# 1V8_3V3_5V.net
KiCad netlist of a schematic drawn in Altium Designer
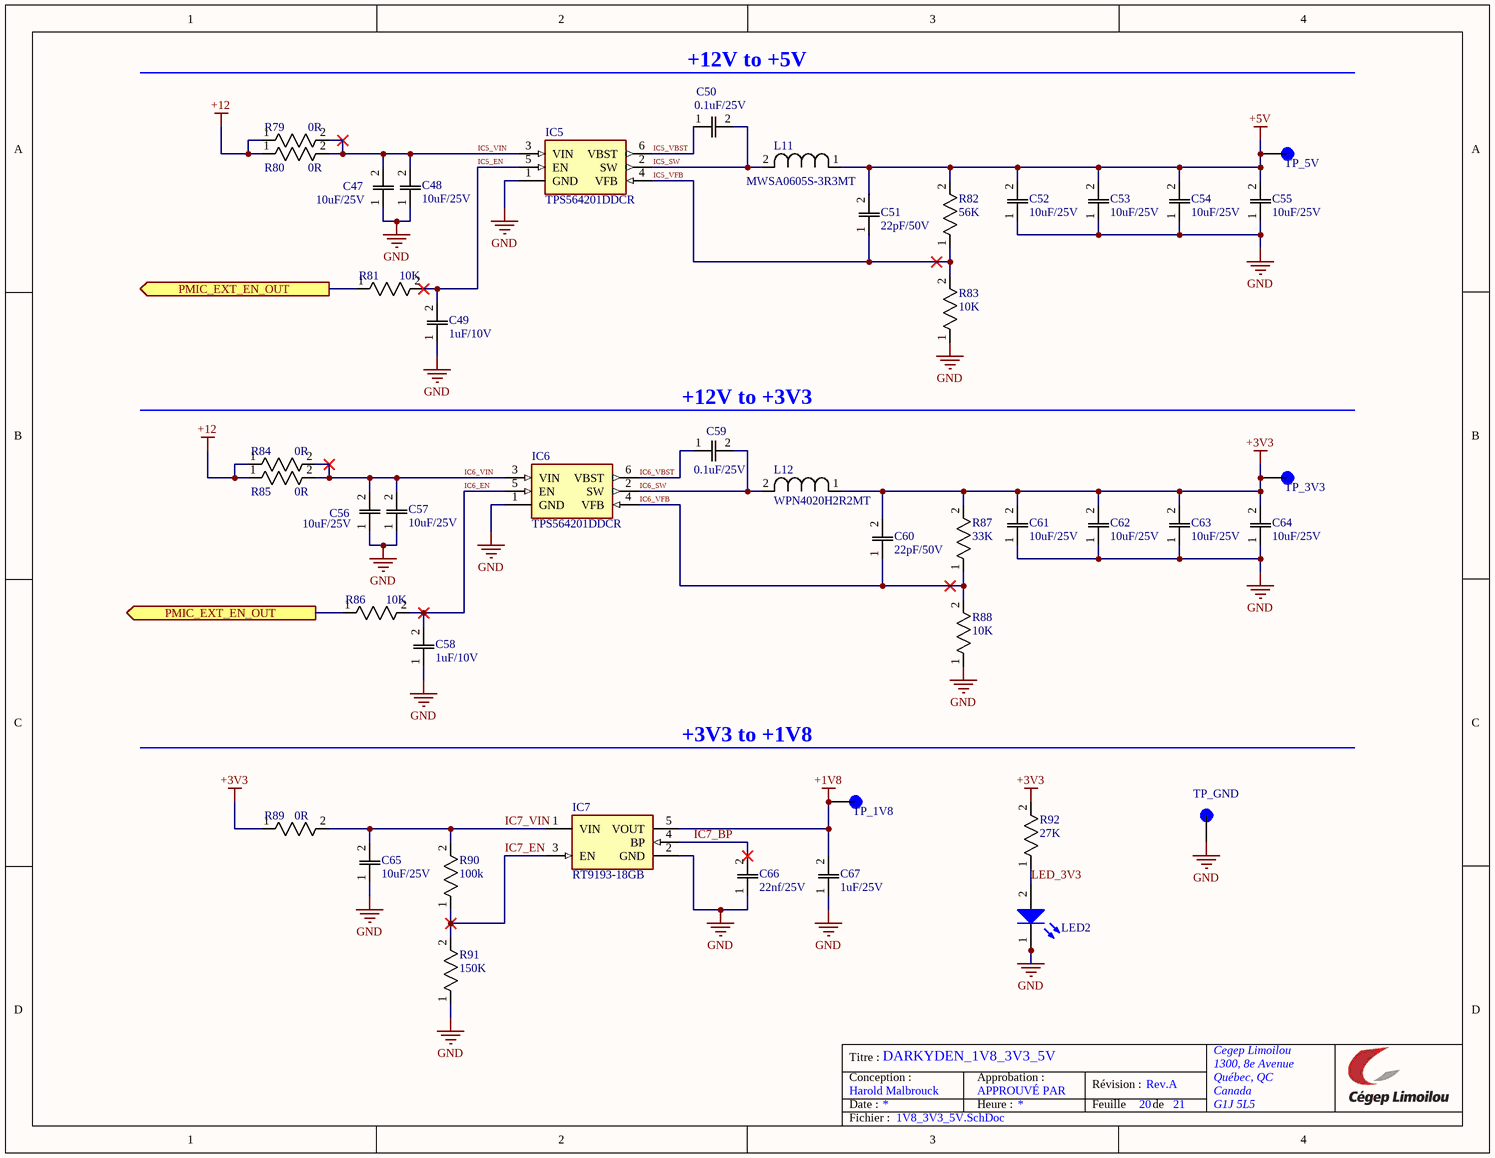
[diagram p0: 1V8_3V3_5V.SchDoc]

(export (version "E")
  (design (tool "Eeschema 10.0.6"))
  (components
    (comp (ref "C47")
      (value "10uF/25V")
      (footprint "C0805")
      (description "10uF / 25 VDC, +85degC, X5R Dielec, +/-10% ¦ KEMET C0805C106K3PACTU 0805")
      (fields
        (field (name "MANUFACTURER") "KEMET")
        (field (name "MANUFACTURER PART NUMBER") "C0805C106K3PACTU")
      )
      (libsource (lib "DARKYDEN") (part "C0805C106K3PACTU"))
    )
    (comp (ref "C48")
      (value "10uF/25V")
      (footprint "C0805")
      (description "10uF / 25 VDC, +85degC, X5R Dielec, +/-10% ¦ KEMET C0805C106K3PACTU 0805")
      (fields
        (field (name "MANUFACTURER") "KEMET")
        (field (name "MANUFACTURER PART NUMBER") "C0805C106K3PACTU")
      )
      (libsource (lib "DARKYDEN") (part "C0805C106K3PACTU"))
    )
    (comp (ref "C49")
      (value "1uF/10V")
      (footprint "C0805")
      (description "Multilayer Ceramic Capacitors MLCC - SMD/SMT 10V 1uF X7R 0805 10%")
      (fields
        (field (name "MANUFACTURER") "KEMET")
        (field (name "MANUFACTURER PART NUMBER") "C0805C105K3RACTU")
      )
      (libsource (lib "DARKYDEN") (part "C0805C105K8RACTU"))
    )
    (comp (ref "C50")
      (value "0.1uF/25V")
      (footprint "c0805")
      (description "0.1uF 25V X7R 10% SMD 0805 125C Plastic T/R")
      (fields
        (field (name "MANUFACTURER") "KEMET")
        (field (name "MANUFACTURER PART NUMBER") "C0805C104K5RACTU")
      )
      (libsource (lib "DARKYDEN") (part "C0805C104K3RACTU"))
    )
    (comp (ref "C51")
      (value "22pF/50V")
      (footprint "C0805")
      (description "Cap Ceramic 22pF 50V X7R 5% Pad SMD 0805 125°C T/R")
      (fields
        (field (name "MANUFACTURER") "KEMET")
        (field (name "MANUFACTURER PART NUMBER") "C0805C220J5RACTU")
      )
      (libsource (lib "DARKYDEN") (part "C0805C220J5RACTU"))
    )
    (comp (ref "C52")
      (value "10uF/25V")
      (footprint "C0805")
      (description "10uF / 25 VDC, +85degC, X5R Dielec, +/-10% ¦ KEMET C0805C106K3PACTU 0805")
      (fields
        (field (name "MANUFACTURER") "KEMET")
        (field (name "MANUFACTURER PART NUMBER") "C0805C106K3PACTU")
      )
      (libsource (lib "DARKYDEN") (part "C0805C106K3PACTU"))
    )
    (comp (ref "C53")
      (value "10uF/25V")
      (footprint "C0805")
      (description "10uF / 25 VDC, +85degC, X5R Dielec, +/-10% ¦ KEMET C0805C106K3PACTU 0805")
      (fields
        (field (name "MANUFACTURER") "KEMET")
        (field (name "MANUFACTURER PART NUMBER") "C0805C106K3PACTU")
      )
      (libsource (lib "DARKYDEN") (part "C0805C106K3PACTU"))
    )
    (comp (ref "C54")
      (value "10uF/25V")
      (footprint "C0805")
      (description "10uF / 25 VDC, +85degC, X5R Dielec, +/-10% ¦ KEMET C0805C106K3PACTU 0805")
      (fields
        (field (name "MANUFACTURER") "KEMET")
        (field (name "MANUFACTURER PART NUMBER") "C0805C106K3PACTU")
      )
      (libsource (lib "DARKYDEN") (part "C0805C106K3PACTU"))
    )
    (comp (ref "C55")
      (value "10uF/25V")
      (footprint "C0805")
      (description "10uF / 25 VDC, +85degC, X5R Dielec, +/-10% ¦ KEMET C0805C106K3PACTU 0805")
      (fields
        (field (name "MANUFACTURER") "KEMET")
        (field (name "MANUFACTURER PART NUMBER") "C0805C106K3PACTU")
      )
      (libsource (lib "DARKYDEN") (part "C0805C106K3PACTU"))
    )
    (comp (ref "C56")
      (value "10uF/25V")
      (footprint "C0805")
      (description "10uF / 25 VDC, +85degC, X5R Dielec, +/-10% ¦ KEMET C0805C106K3PACTU 0805")
      (fields
        (field (name "MANUFACTURER") "KEMET")
        (field (name "MANUFACTURER PART NUMBER") "C0805C106K3PACTU")
      )
      (libsource (lib "DARKYDEN") (part "C0805C106K3PACTU"))
    )
    (comp (ref "C57")
      (value "10uF/25V")
      (footprint "C0805")
      (description "10uF / 25 VDC, +85degC, X5R Dielec, +/-10% ¦ KEMET C0805C106K3PACTU 0805")
      (fields
        (field (name "MANUFACTURER") "KEMET")
        (field (name "MANUFACTURER PART NUMBER") "C0805C106K3PACTU")
      )
      (libsource (lib "DARKYDEN") (part "C0805C106K3PACTU"))
    )
    (comp (ref "C58")
      (value "1uF/10V")
      (footprint "C0805")
      (description "Multilayer Ceramic Capacitors MLCC - SMD/SMT 10V 1uF X7R 0805 10%")
      (fields
        (field (name "MANUFACTURER") "KEMET")
        (field (name "MANUFACTURER PART NUMBER") "C0805C105K3RACTU")
      )
      (libsource (lib "DARKYDEN") (part "C0805C105K8RACTU"))
    )
    (comp (ref "C59")
      (value "0.1uF/25V")
      (footprint "c0805")
      (description "0.1uF 25V X7R 10% SMD 0805 125C Plastic T/R")
      (fields
        (field (name "MANUFACTURER") "KEMET")
        (field (name "MANUFACTURER PART NUMBER") "C0805C104K5RACTU")
      )
      (libsource (lib "DARKYDEN") (part "C0805C104K3RACTU"))
    )
    (comp (ref "C60")
      (value "22pF/50V")
      (footprint "C0805")
      (description "Cap Ceramic 22pF 50V X7R 5% Pad SMD 0805 125°C T/R")
      (fields
        (field (name "MANUFACTURER") "KEMET")
        (field (name "MANUFACTURER PART NUMBER") "C0805C220J5RACTU")
      )
      (libsource (lib "DARKYDEN") (part "C0805C220J5RACTU"))
    )
    (comp (ref "C61")
      (value "10uF/25V")
      (footprint "C0805")
      (description "10uF / 25 VDC, +85degC, X5R Dielec, +/-10% ¦ KEMET C0805C106K3PACTU 0805")
      (fields
        (field (name "MANUFACTURER") "KEMET")
        (field (name "MANUFACTURER PART NUMBER") "C0805C106K3PACTU")
      )
      (libsource (lib "DARKYDEN") (part "C0805C106K3PACTU"))
    )
    (comp (ref "C62")
      (value "10uF/25V")
      (footprint "C0805")
      (description "10uF / 25 VDC, +85degC, X5R Dielec, +/-10% ¦ KEMET C0805C106K3PACTU 0805")
      (fields
        (field (name "MANUFACTURER") "KEMET")
        (field (name "MANUFACTURER PART NUMBER") "C0805C106K3PACTU")
      )
      (libsource (lib "DARKYDEN") (part "C0805C106K3PACTU"))
    )
    (comp (ref "C63")
      (value "10uF/25V")
      (footprint "C0805")
      (description "10uF / 25 VDC, +85degC, X5R Dielec, +/-10% ¦ KEMET C0805C106K3PACTU 0805")
      (fields
        (field (name "MANUFACTURER") "KEMET")
        (field (name "MANUFACTURER PART NUMBER") "C0805C106K3PACTU")
      )
      (libsource (lib "DARKYDEN") (part "C0805C106K3PACTU"))
    )
    (comp (ref "C64")
      (value "10uF/25V")
      (footprint "C0805")
      (description "10uF / 25 VDC, +85degC, X5R Dielec, +/-10% ¦ KEMET C0805C106K3PACTU 0805")
      (fields
        (field (name "MANUFACTURER") "KEMET")
        (field (name "MANUFACTURER PART NUMBER") "C0805C106K3PACTU")
      )
      (libsource (lib "DARKYDEN") (part "C0805C106K3PACTU"))
    )
    (comp (ref "C65")
      (value "10uF/25V")
      (footprint "C0805")
      (description "10uF / 25 VDC, +85degC, X5R Dielec, +/-10% ¦ KEMET C0805C106K3PACTU 0805")
      (fields
        (field (name "MANUFACTURER") "KEMET")
        (field (name "MANUFACTURER PART NUMBER") "C0805C106K3PACTU")
      )
      (libsource (lib "DARKYDEN") (part "C0805C106K3PACTU"))
    )
    (comp (ref "C66")
      (value "22nf/25V")
      (footprint "C0805")
      (description "22nF, 25 V, 0805 [2012 Metric], 5%, C0G / NP0")
      (fields
        (field (name "MANUFACTURER") "KEMET")
        (field (name "MANUFACTURER PART NUMBER") "C0805C223J3GACTU")
      )
      (libsource (lib "DARKYDEN") (part "C0805C223J3GACTU"))
    )
    (comp (ref "C67")
      (value "1uF/25V")
      (footprint "C0805")
      (description "1 µF, 25 V (DC), ±10 %, SMD 0805, X7R, C0805C105K3RAC7800")
      (fields
        (field (name "MOUSER PART NUMBER") "80-C0805C105K3R")
        (field (name "ARROW PART NUMBER") "C0805C105K3RACTU")
      )
      (libsource (lib "DARKYDEN") (part "C0805C105K3RACTU"))
    )
    (comp (ref "IC5")
      (value "TPS564201DDCR")
      (footprint "SamacSys:SOT95P280X110-6N")
      (fields
        (field (name "MOUSER PART NUMBER") "595-TPS564201DDCR")
        (field (name "MANUFACTURER") "Texas Instruments")
      )
      (libsource (lib "SamacSys") (part "TPS564201DDCR"))
    )
    (comp (ref "IC6")
      (value "TPS564201DDCR")
      (footprint "SamacSys:SOT95P280X110-6N")
      (fields
        (field (name "MOUSER PART NUMBER") "595-TPS564201DDCR")
        (field (name "MANUFACTURER") "Texas Instruments")
      )
      (libsource (lib "SamacSys") (part "TPS564201DDCR"))
    )
    (comp (ref "IC7")
      (value "RT9193-18GB")
      (footprint "SamacSys:SOT94P279X130-5N")
      (description "Linear Voltage Regulator IC Positive Fixed 1.8V Output 300mA SOT-23-5")
      (fields (field (name "MOUSER PART NUMBER") "835-RT9193-18GB"))
      (libsource (lib "SamacSys") (part "RT9193-18GB"))
    )
    (comp (ref "L11")
      (value "MWSA0605S-3R3MT")
      (footprint "IND_MWSA0603S_SNL")
      (description "3.3 µH Shielded Drum Core, Wirewound Inductor 8.5 A 22mOhm Max Nonstandard")
      (libsource (lib "MWSA0603S-XRXMT") (part "MWSA0605S-3R3MT"))
    )
    (comp (ref "L12")
      (value "WPN4020H2R2MT")
      (footprint "WPN4020H2R2MT:IND_WPN4020H_SNL")
      (description "2.2 µH Shielded Drum Core, Wirewound Inductor 4.3 A 48mOhm Max Nonstandard")
      (fields (field (name "MANUFACTURER") "Sunlord"))
      (libsource (lib "DARKYDEN") (part "WPN4020H2R2MT"))
    )
    (comp (ref "LED2")
      (value "Blue, 3.2V, 140°")
      (footprint "WL-SMCD_0603")
      (description "WL-SMCD Mono-color Chip LED Diffused, SMT, size 0603, Blue, 3.2V, 140°")
      (fields
        (field (name "MANUFACTURER PART NUMBER") "150060BS55040")
        (field (name "MANUFACTURER") "Wurth Elektronik")
      )
      (libsource (lib "0603_LED") (part "BLUE"))
    )
    (comp (ref "R79")
      (value "0R")
      (footprint "SamacSys:RESC1608X55N")
      (description "Zero Ohm Resistor, Jumper, 0603 [1608 Metric], Thick Film, 100 mW, 1 A, Surface Mount")
      (fields
        (field (name "MOUSER PART NUMBER") "667-ERJ-3GEY0R00V")
        (field (name "ARROW PART NUMBER") "ERJ-3GEY0R00V")
      )
      (libsource (lib "DARKYDEN") (part "ERJ-3GEY0R00V"))
    )
    (comp (ref "R80")
      (value "0R")
      (footprint "SamacSys:RESC1608X55N")
      (description "Zero Ohm Resistor, Jumper, 0603 [1608 Metric], Thick Film, 100 mW, 1 A, Surface Mount")
      (fields
        (field (name "MOUSER PART NUMBER") "667-ERJ-3GEY0R00V")
        (field (name "ARROW PART NUMBER") "ERJ-3GEY0R00V")
      )
      (libsource (lib "DARKYDEN") (part "ERJ-3GEY0R00V"))
    )
    (comp (ref "R81")
      (value "10K")
      (footprint "SamacSys:RESC1608X55N")
      (description "10K Ohm 5% Res Thick Film 0603  0.1W(1/10W) ±200ppm/C Pad SMD Automotive T/R")
      (fields
        (field (name "MOUSER PART NUMBER") "667-ERJ-3GEYJ103V")
        (field (name "ARROW PART NUMBER") "ERJ-3GEYJ103V")
      )
      (libsource (lib "DARKYDEN") (part "ERJ-3GEYJ103V"))
    )
    (comp (ref "R82")
      (value "56K")
      (footprint "SamacSys:RESC1608X55N")
      (description "56K Ohm 1% 1/10W +/-100ppm/ßC Molded SMD Punched Carrier T/R")
      (fields
        (field (name "MOUSER PART NUMBER") "667-ERJ-3EKF5602V")
        (field (name "ARROW PART NUMBER") "ERJ-3EKF5602V")
      )
      (libsource (lib "DARKYDEN") (part "ERJ-3EKF5602V"))
    )
    (comp (ref "R83")
      (value "10K")
      (footprint "SamacSys:RESC1608X55N")
      (description "10K Ohm 5% Res Thick Film 0603  0.1W(1/10W) ±200ppm/C Pad SMD Automotive T/R")
      (fields
        (field (name "MOUSER PART NUMBER") "667-ERJ-3GEYJ103V")
        (field (name "ARROW PART NUMBER") "ERJ-3GEYJ103V")
      )
      (libsource (lib "DARKYDEN") (part "ERJ-3GEYJ103V"))
    )
    (comp (ref "R84")
      (value "0R")
      (footprint "SamacSys:RESC1608X55N")
      (description "Zero Ohm Resistor, Jumper, 0603 [1608 Metric], Thick Film, 100 mW, 1 A, Surface Mount")
      (fields
        (field (name "MOUSER PART NUMBER") "667-ERJ-3GEY0R00V")
        (field (name "ARROW PART NUMBER") "ERJ-3GEY0R00V")
      )
      (libsource (lib "DARKYDEN") (part "ERJ-3GEY0R00V"))
    )
    (comp (ref "R85")
      (value "0R")
      (footprint "SamacSys:RESC1608X55N")
      (description "Zero Ohm Resistor, Jumper, 0603 [1608 Metric], Thick Film, 100 mW, 1 A, Surface Mount")
      (fields
        (field (name "MOUSER PART NUMBER") "667-ERJ-3GEY0R00V")
        (field (name "ARROW PART NUMBER") "ERJ-3GEY0R00V")
      )
      (libsource (lib "DARKYDEN") (part "ERJ-3GEY0R00V"))
    )
    (comp (ref "R86")
      (value "10K")
      (footprint "SamacSys:RESC1608X55N")
      (description "10K Ohm 5% Res Thick Film 0603  0.1W(1/10W) ±200ppm/C Pad SMD Automotive T/R")
      (fields
        (field (name "MOUSER PART NUMBER") "667-ERJ-3GEYJ103V")
        (field (name "ARROW PART NUMBER") "ERJ-3GEYJ103V")
      )
      (libsource (lib "DARKYDEN") (part "ERJ-3GEYJ103V"))
    )
    (comp (ref "R87")
      (value "33K")
      (footprint "SamacSys:RESC1608X55N")
      (description "33K Ohm 0603  5% 0.1W(1/10W) +/-200ppm/ßC SMD Automotive T/R")
      (fields
        (field (name "MOUSER PART NUMBER") "667-ERJ-3GEYJ333V")
        (field (name "MANUFACTURER") "Panasonic")
      )
      (libsource (lib "DARKYDEN") (part "ERJ-3GEYJ333V"))
    )
    (comp (ref "R88")
      (value "10K")
      (footprint "SamacSys:RESC1608X55N")
      (description "10K Ohm 5% Res Thick Film 0603  0.1W(1/10W) ±200ppm/C Pad SMD Automotive T/R")
      (fields
        (field (name "MOUSER PART NUMBER") "667-ERJ-3GEYJ103V")
        (field (name "ARROW PART NUMBER") "ERJ-3GEYJ103V")
      )
      (libsource (lib "DARKYDEN") (part "ERJ-3GEYJ103V"))
    )
    (comp (ref "R89")
      (value "0R")
      (footprint "SamacSys:RESC1608X55N")
      (description "Zero Ohm Resistor, Jumper, 0603 [1608 Metric], Thick Film, 100 mW, 1 A, Surface Mount")
      (fields
        (field (name "MOUSER PART NUMBER") "667-ERJ-3GEY0R00V")
        (field (name "ARROW PART NUMBER") "ERJ-3GEY0R00V")
      )
      (libsource (lib "DARKYDEN") (part "ERJ-3GEY0R00V"))
    )
    (comp (ref "R90")
      (value "100k")
      (footprint "SamacSys:RESC1608X55N")
      (description "100K Ohm 5%  Res Thick Film 0603 1/10W +/-200ppm/ßC Molded SMD Punched Carrier T/R")
      (fields
        (field (name "MOUSER PART NUMBER") "667-ERJ-3GEYJ104V")
        (field (name "ARROW PART NUMBER") "ERJ-3GEYJ104V")
      )
      (libsource (lib "DARKYDEN") (part "ERJ-3GEYJ104V"))
    )
    (comp (ref "R91")
      (value "150K")
      (footprint "SamacSys:RESC1608X55N")
      (description "150 kOhm, ± 5%, 100 mW, 0603 [1608 Metric], Thick Film, General Purpose")
      (fields
        (field (name "MOUSER PART NUMBER") "667-ERJ-3GEYJ154V")
        (field (name "ARROW PART NUMBER") "ERJ-3GEYJ154V")
      )
      (libsource (lib "DARKYDEN") (part "ERJ-3GEYJ154V"))
    )
    (comp (ref "R92")
      (value "27K")
      (footprint "RESC1608X55N")
      (description "27K Ohm 1% 1/10W 0603 ±100ppm/°C Molded SMD Punched Carrier T/R")
      (fields
        (field (name "MANUFACTURER") "Panasonic")
        (field (name "MANUFACTURER PART NUMBER") "ERJ-3EKF2702V")
      )
      (libsource (lib "DARKYDEN") (part "ERJ-3EKF2702V"))
    )
    (comp (ref "TP_1V8")
      (value "~")
      (footprint "KEYSTONE_5006")
      (description "Test Point Compact THM PC .350 L .125 OD Heat Resistant Nylon 46 Black ¦ Keystone Electronics 5006")
      (fields (field (name "MF") "Keystone Electronics Corp.") (field (name "MP") "5006"))
      (libsource (lib "DARKYDEN") (part "5006"))
    )
    (comp (ref "TP_3V3")
      (value "~")
      (footprint "KEYSTONE_5006")
      (description "Test Point Compact THM PC .350 L .125 OD Heat Resistant Nylon 46 Black ¦ Keystone Electronics 5006")
      (fields (field (name "MF") "Keystone Electronics Corp.") (field (name "MP") "5006"))
      (libsource (lib "DARKYDEN") (part "5006"))
    )
    (comp (ref "TP_5V")
      (value "~")
      (footprint "KEYSTONE_5006")
      (description "Test Point Compact THM PC .350 L .125 OD Heat Resistant Nylon 46 Black ¦ Keystone Electronics 5006")
      (fields (field (name "MF") "Keystone Electronics Corp.") (field (name "MP") "5006"))
      (libsource (lib "DARKYDEN") (part "5006"))
    )
    (comp (ref "TP_GND")
      (value "~")
      (footprint "KEYSTONE_5006")
      (description "Test Point Compact THM PC .350 L .125 OD Heat Resistant Nylon 46 Black ¦ Keystone Electronics 5006")
      (fields (field (name "MF") "Keystone Electronics Corp.") (field (name "MP") "5006"))
      (libsource (lib "DARKYDEN") (part "5006"))
    )
  )
  (nets
    (net (code "1") (name "+1V8") (class "Default")
      (node (ref "C67") (pin "2") (pinfunction "2_2") (pintype "passive"))
      (node (ref "IC7") (pin "5") (pinfunction "VOUT_5") (pintype "power_in"))
      (node (ref "TP_1V8") (pin "TP") (pinfunction "TP_TP") (pintype "passive"))
    )
    (net (code "2") (name "+3V3") (class "Default")
      (node (ref "C60") (pin "2") (pinfunction "2_2") (pintype "passive"))
      (node (ref "C61") (pin "2") (pinfunction "2_2") (pintype "passive"))
      (node (ref "C62") (pin "2") (pinfunction "2_2") (pintype "passive"))
      (node (ref "C63") (pin "2") (pinfunction "2_2") (pintype "passive"))
      (node (ref "C64") (pin "2") (pinfunction "2_2") (pintype "passive"))
      (node (ref "L12") (pin "1") (pinfunction "1_1") (pintype "passive"))
      (node (ref "R87") (pin "2") (pinfunction "2_2") (pintype "passive"))
      (node (ref "R89") (pin "1") (pinfunction "1_1") (pintype "passive"))
      (node (ref "R92") (pin "2") (pinfunction "2_2") (pintype "passive"))
      (node (ref "TP_3V3") (pin "TP") (pinfunction "TP_TP") (pintype "passive"))
    )
    (net (code "3") (name "+5V") (class "Default")
      (node (ref "C51") (pin "2") (pinfunction "2_2") (pintype "passive"))
      (node (ref "C52") (pin "2") (pinfunction "2_2") (pintype "passive"))
      (node (ref "C53") (pin "2") (pinfunction "2_2") (pintype "passive"))
      (node (ref "C54") (pin "2") (pinfunction "2_2") (pintype "passive"))
      (node (ref "C55") (pin "2") (pinfunction "2_2") (pintype "passive"))
      (node (ref "L11") (pin "1") (pinfunction "1_1") (pintype "passive"))
      (node (ref "R82") (pin "2") (pinfunction "2_2") (pintype "passive"))
      (node (ref "TP_5V") (pin "TP") (pinfunction "TP_TP") (pintype "passive"))
    )
    (net (code "4") (name "+12") (class "Default")
      (node (ref "R79") (pin "1") (pinfunction "1_1") (pintype "passive"))
      (node (ref "R80") (pin "1") (pinfunction "1_1") (pintype "passive"))
      (node (ref "R84") (pin "1") (pinfunction "1_1") (pintype "passive"))
      (node (ref "R85") (pin "1") (pinfunction "1_1") (pintype "passive"))
    )
    (net (code "5") (name "/IC5_EN") (class "Default")
      (node (ref "C49") (pin "2") (pinfunction "2_2") (pintype "passive"))
      (node (ref "IC5") (pin "5") (pinfunction "EN_5") (pintype "input"))
      (node (ref "R81") (pin "2") (pinfunction "2_2") (pintype "passive"))
    )
    (net (code "6") (name "/IC5_SW") (class "Default")
      (node (ref "C50") (pin "2") (pinfunction "2_2") (pintype "passive"))
      (node (ref "IC5") (pin "2") (pinfunction "SW_2") (pintype "output"))
      (node (ref "L11") (pin "2") (pinfunction "2_2") (pintype "passive"))
    )
    (net (code "7") (name "/IC5_VBST") (class "Default")
      (node (ref "C50") (pin "1") (pinfunction "1_1") (pintype "passive"))
      (node (ref "IC5") (pin "6") (pinfunction "VBST_6") (pintype "output"))
    )
    (net (code "8") (name "/IC5_VFB") (class "Default")
      (node (ref "C51") (pin "1") (pinfunction "1_1") (pintype "passive"))
      (node (ref "IC5") (pin "4") (pinfunction "VFB_4") (pintype "input"))
      (node (ref "R82") (pin "1") (pinfunction "1_1") (pintype "passive"))
      (node (ref "R83") (pin "2") (pinfunction "2_2") (pintype "passive"))
    )
    (net (code "9") (name "/IC5_VIN") (class "Default")
      (node (ref "C47") (pin "2") (pinfunction "2_2") (pintype "passive"))
      (node (ref "C48") (pin "2") (pinfunction "2_2") (pintype "passive"))
      (node (ref "IC5") (pin "3") (pinfunction "VIN_3") (pintype "input"))
      (node (ref "R79") (pin "2") (pinfunction "2_2") (pintype "passive"))
      (node (ref "R80") (pin "2") (pinfunction "2_2") (pintype "passive"))
    )
    (net (code "10") (name "/IC6_EN") (class "Default")
      (node (ref "C58") (pin "2") (pinfunction "2_2") (pintype "passive"))
      (node (ref "IC6") (pin "5") (pinfunction "EN_5") (pintype "input"))
      (node (ref "R86") (pin "2") (pinfunction "2_2") (pintype "passive"))
    )
    (net (code "11") (name "/IC6_SW") (class "Default")
      (node (ref "C59") (pin "2") (pinfunction "2_2") (pintype "passive"))
      (node (ref "IC6") (pin "2") (pinfunction "SW_2") (pintype "output"))
      (node (ref "L12") (pin "2") (pinfunction "2_2") (pintype "passive"))
    )
    (net (code "12") (name "/IC6_VBST") (class "Default")
      (node (ref "C59") (pin "1") (pinfunction "1_1") (pintype "passive"))
      (node (ref "IC6") (pin "6") (pinfunction "VBST_6") (pintype "output"))
    )
    (net (code "13") (name "/IC6_VFB") (class "Default")
      (node (ref "C60") (pin "1") (pinfunction "1_1") (pintype "passive"))
      (node (ref "IC6") (pin "4") (pinfunction "VFB_4") (pintype "input"))
      (node (ref "R87") (pin "1") (pinfunction "1_1") (pintype "passive"))
      (node (ref "R88") (pin "2") (pinfunction "2_2") (pintype "passive"))
    )
    (net (code "14") (name "/IC6_VIN") (class "Default")
      (node (ref "C56") (pin "2") (pinfunction "2_2") (pintype "passive"))
      (node (ref "C57") (pin "2") (pinfunction "2_2") (pintype "passive"))
      (node (ref "IC6") (pin "3") (pinfunction "VIN_3") (pintype "input"))
      (node (ref "R84") (pin "2") (pinfunction "2_2") (pintype "passive"))
      (node (ref "R85") (pin "2") (pinfunction "2_2") (pintype "passive"))
    )
    (net (code "15") (name "/IC7_BP") (class "Default")
      (node (ref "C66") (pin "2") (pinfunction "2_2") (pintype "passive"))
      (node (ref "IC7") (pin "4") (pinfunction "BP_4") (pintype "input"))
    )
    (net (code "16") (name "/IC7_EN") (class "Default")
      (node (ref "IC7") (pin "3") (pinfunction "EN_3") (pintype "input"))
      (node (ref "R90") (pin "1") (pinfunction "1_1") (pintype "passive"))
      (node (ref "R91") (pin "2") (pinfunction "2_2") (pintype "passive"))
    )
    (net (code "17") (name "/IC7_VIN") (class "Default")
      (node (ref "C65") (pin "2") (pinfunction "2_2") (pintype "passive"))
      (node (ref "IC7") (pin "1") (pinfunction "VIN_1") (pintype "power_in"))
      (node (ref "R89") (pin "2") (pinfunction "2_2") (pintype "passive"))
      (node (ref "R90") (pin "2") (pinfunction "2_2") (pintype "passive"))
    )
    (net (code "18") (name "/LED_3V3") (class "Default")
      (node (ref "LED2") (pin "2") (pinfunction "A_2") (pintype "passive"))
      (node (ref "R92") (pin "1") (pinfunction "1_1") (pintype "passive"))
    )
    (net (code "19") (name "/PMIC_EXT_EN_OUT") (class "Default")
      (node (ref "R81") (pin "1") (pinfunction "1_1") (pintype "passive"))
      (node (ref "R86") (pin "1") (pinfunction "1_1") (pintype "passive"))
    )
    (net (code "20") (name "GND") (class "Default")
      (node (ref "C47") (pin "1") (pinfunction "1_1") (pintype "passive"))
      (node (ref "C48") (pin "1") (pinfunction "1_1") (pintype "passive"))
      (node (ref "C49") (pin "1") (pinfunction "1_1") (pintype "passive"))
      (node (ref "C52") (pin "1") (pinfunction "1_1") (pintype "passive"))
      (node (ref "C53") (pin "1") (pinfunction "1_1") (pintype "passive"))
      (node (ref "C54") (pin "1") (pinfunction "1_1") (pintype "passive"))
      (node (ref "C55") (pin "1") (pinfunction "1_1") (pintype "passive"))
      (node (ref "C56") (pin "1") (pinfunction "1_1") (pintype "passive"))
      (node (ref "C57") (pin "1") (pinfunction "1_1") (pintype "passive"))
      (node (ref "C58") (pin "1") (pinfunction "1_1") (pintype "passive"))
      (node (ref "C61") (pin "1") (pinfunction "1_1") (pintype "passive"))
      (node (ref "C62") (pin "1") (pinfunction "1_1") (pintype "passive"))
      (node (ref "C63") (pin "1") (pinfunction "1_1") (pintype "passive"))
      (node (ref "C64") (pin "1") (pinfunction "1_1") (pintype "passive"))
      (node (ref "C65") (pin "1") (pinfunction "1_1") (pintype "passive"))
      (node (ref "C66") (pin "1") (pinfunction "1_1") (pintype "passive"))
      (node (ref "C67") (pin "1") (pinfunction "1_1") (pintype "passive"))
      (node (ref "IC5") (pin "1") (pinfunction "GND_1") (pintype "passive"))
      (node (ref "IC6") (pin "1") (pinfunction "GND_1") (pintype "passive"))
      (node (ref "IC7") (pin "2") (pinfunction "GND_2") (pintype "passive"))
      (node (ref "LED2") (pin "1") (pinfunction "K_1") (pintype "passive"))
      (node (ref "R83") (pin "1") (pinfunction "1_1") (pintype "passive"))
      (node (ref "R88") (pin "1") (pinfunction "1_1") (pintype "passive"))
      (node (ref "R91") (pin "1") (pinfunction "1_1") (pintype "passive"))
      (node (ref "TP_GND") (pin "TP") (pinfunction "TP_TP") (pintype "passive"))
    )
  )
)
